# Connectors.net
KiCad netlist of a schematic drawn in Altium Designer
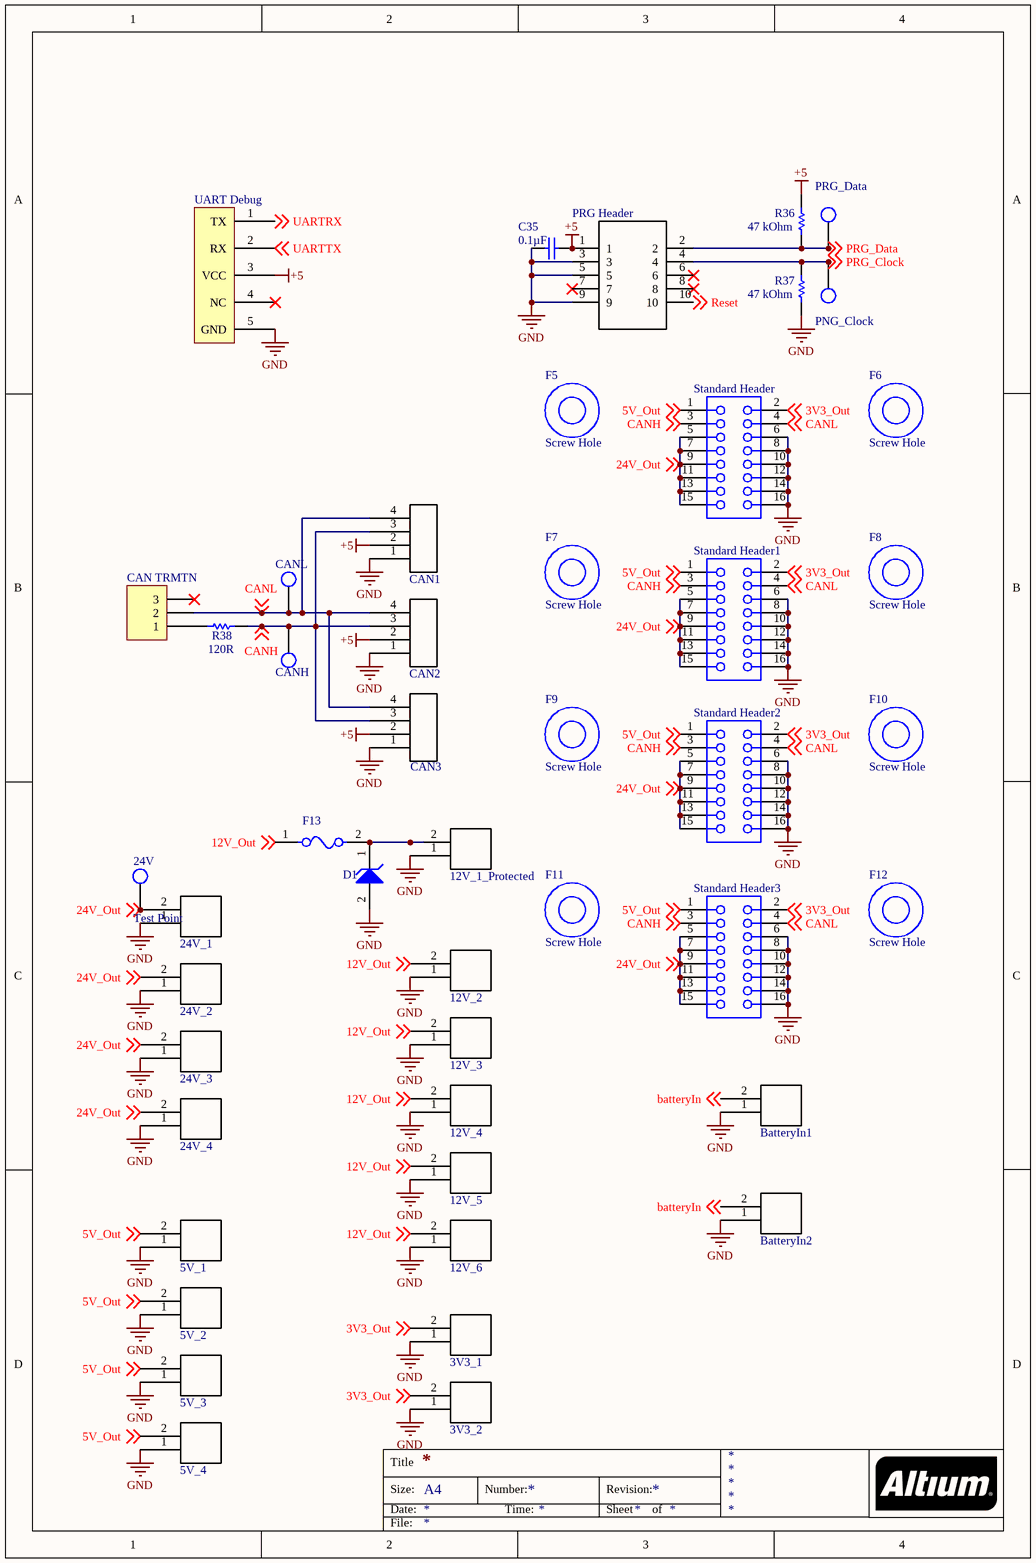
[diagram p0: Connectors.SchDoc]

(export (version "E")
  (design (tool "Eeschema 10.0.6"))
  (components
    (comp (ref "3V3_1")
      (value "Molex 6.5MM  power connector")
      (footprint "power connector")
      (libsource (lib "Husky Robotics Standard Library 2019-2020") (part "Molex 6.5MM  power connector"))
    )
    (comp (ref "3V3_2")
      (value "Molex 6.5MM  power connector")
      (footprint "power connector")
      (libsource (lib "Husky Robotics Standard Library 2019-2020") (part "Molex 6.5MM  power connector"))
    )
    (comp (ref "5V_1")
      (value "Molex 6.5MM  power connector")
      (footprint "power connector")
      (libsource (lib "Husky Robotics Standard Library 2019-2020") (part "Molex 6.5MM  power connector"))
    )
    (comp (ref "5V_2")
      (value "Molex 6.5MM  power connector")
      (footprint "power connector")
      (libsource (lib "Husky Robotics Standard Library 2019-2020") (part "Molex 6.5MM  power connector"))
    )
    (comp (ref "5V_3")
      (value "Molex 6.5MM  power connector")
      (footprint "power connector")
      (libsource (lib "Husky Robotics Standard Library 2019-2020") (part "Molex 6.5MM  power connector"))
    )
    (comp (ref "5V_4")
      (value "Molex 6.5MM  power connector")
      (footprint "power connector")
      (libsource (lib "Husky Robotics Standard Library 2019-2020") (part "Molex 6.5MM  power connector"))
    )
    (comp (ref "12V_1_Protected")
      (value "Molex 6.5MM  power connector")
      (footprint "power connector")
      (libsource (lib "Husky Robotics Standard Library 2019-2020") (part "Molex 6.5MM  power connector"))
    )
    (comp (ref "12V_2")
      (value "Molex 6.5MM  power connector")
      (footprint "power connector")
      (libsource (lib "Husky Robotics Standard Library 2019-2020") (part "Molex 6.5MM  power connector"))
    )
    (comp (ref "12V_3")
      (value "Molex 6.5MM  power connector")
      (footprint "power connector")
      (libsource (lib "Husky Robotics Standard Library 2019-2020") (part "Molex 6.5MM  power connector"))
    )
    (comp (ref "12V_4")
      (value "Molex 6.5MM  power connector")
      (footprint "power connector")
      (libsource (lib "Husky Robotics Standard Library 2019-2020") (part "Molex 6.5MM  power connector"))
    )
    (comp (ref "12V_5")
      (value "Molex 6.5MM  power connector")
      (footprint "power connector")
      (libsource (lib "Husky Robotics Standard Library 2019-2020") (part "Molex 6.5MM  power connector"))
    )
    (comp (ref "12V_6")
      (value "Molex 6.5MM  power connector")
      (footprint "power connector")
      (libsource (lib "Husky Robotics Standard Library 2019-2020") (part "Molex 6.5MM  power connector"))
    )
    (comp (ref "24V")
      (value "Test Point")
      (footprint "Test Point Through-hole")
      (libsource (lib "University of Washington - Husky Robotics Team") (part "Test Point"))
    )
    (comp (ref "24V_1")
      (value "Molex 6.5MM  power connector")
      (footprint "power connector")
      (libsource (lib "Husky Robotics Standard Library 2019-2020") (part "Molex 6.5MM  power connector"))
    )
    (comp (ref "24V_2")
      (value "Molex 6.5MM  power connector")
      (footprint "power connector")
      (libsource (lib "Husky Robotics Standard Library 2019-2020") (part "Molex 6.5MM  power connector"))
    )
    (comp (ref "24V_3")
      (value "Molex 6.5MM  power connector")
      (footprint "power connector")
      (libsource (lib "Husky Robotics Standard Library 2019-2020") (part "Molex 6.5MM  power connector"))
    )
    (comp (ref "24V_4")
      (value "Molex 6.5MM  power connector")
      (footprint "power connector")
      (libsource (lib "Husky Robotics Standard Library 2019-2020") (part "Molex 6.5MM  power connector"))
    )
    (comp (ref "BatteryIn1")
      (value "Super Saber")
      (footprint "Super Sabre")
      (libsource (lib "Husky Robotics Standard Library 2019-2020") (part "Super Saber"))
    )
    (comp (ref "BatteryIn2")
      (value "Super Saber")
      (footprint "Super Sabre")
      (libsource (lib "Husky Robotics Standard Library 2019-2020") (part "Super Saber"))
    )
    (comp (ref "C35")
      (value "Capacitor 0805")
      (footprint "Cap 0805")
      (description "Standard Capacitor")
      (fields (field (name "MANUFACTURER") "AVX") (field (name "CAPACITANCE") "0.1µF"))
      (libsource (lib "Standard Cap") (part "Capacitor 0805"))
    )
    (comp (ref "CAN TRMTN")
      (value "Header 3")
      (footprint "HDR1X3")
      (description "Header, 3-Pin")
      (fields (field (name "PUBLISHER") "Altium Limited"))
      (libsource (lib "Miscellaneous Connectors") (part "Header 3"))
    )
    (comp (ref "CAN1")
      (value "Molex Micro")
      (footprint "microfit 4 pin")
      (description "Molex micro-fit 3.0 dual row header. P/N 0430450427")
      (libsource (lib "Husky Robotics Standard Library 2019-2020") (part "Molex micro-fit 4-pin (Single row schematic)"))
    )
    (comp (ref "CAN2")
      (value "Molex Micro")
      (footprint "microfit 4 pin")
      (description "Molex micro-fit 3.0 dual row header. P/N 0430450427")
      (libsource (lib "Husky Robotics Standard Library 2019-2020") (part "Molex micro-fit 4-pin (Single row schematic)"))
    )
    (comp (ref "CAN3")
      (value "Molex Micro")
      (footprint "microfit 4 pin")
      (description "Molex micro-fit 3.0 dual row header. P/N 0430450427")
      (libsource (lib "Husky Robotics Standard Library 2019-2020") (part "Molex micro-fit 4-pin (Single row schematic)"))
    )
    (comp (ref "CANH")
      (value "Test Point")
      (footprint "Test Point Through-hole")
      (libsource (lib "Husky Robotics Standard Library 2019-2020") (part "Test Point"))
    )
    (comp (ref "CANL")
      (value "Test Point")
      (footprint "Test Point Through-hole")
      (libsource (lib "Husky Robotics Standard Library 2019-2020") (part "Test Point"))
    )
    (comp (ref "D1")
      (value "1SMB5928BT3G")
      (footprint "ONSC-SMB-2-403A-03_H_V")
      (description "3 W Zener Voltage Regulator, 2-Pin SMB, Pb-Free, Tape and Reel")
      (fields (field (name "MANUFACTURER") "On Semiconductor"))
      (libsource (lib "Altium Content Vault") (part "ONSC-K1A2-2"))
    )
    (comp (ref "F5")
      (value "Screw Hole")
      (footprint "Screw Hole")
      (description "Add 4 of these to your design for screw hole mounting")
      (libsource (lib "Husky Robotics Standard Library 2019-2020") (part "Screw Hole"))
    )
    (comp (ref "F6")
      (value "Screw Hole")
      (footprint "Screw Hole")
      (description "Add 4 of these to your design for screw hole mounting")
      (libsource (lib "Husky Robotics Standard Library 2019-2020") (part "Screw Hole"))
    )
    (comp (ref "F7")
      (value "Screw Hole")
      (footprint "Screw Hole")
      (description "Add 4 of these to your design for screw hole mounting")
      (libsource (lib "Husky Robotics Standard Library 2019-2020") (part "Screw Hole"))
    )
    (comp (ref "F8")
      (value "Screw Hole")
      (footprint "Screw Hole")
      (description "Add 4 of these to your design for screw hole mounting")
      (libsource (lib "Husky Robotics Standard Library 2019-2020") (part "Screw Hole"))
    )
    (comp (ref "F9")
      (value "Screw Hole")
      (footprint "Screw Hole")
      (description "Add 4 of these to your design for screw hole mounting")
      (libsource (lib "Husky Robotics Standard Library 2019-2020") (part "Screw Hole"))
    )
    (comp (ref "F10")
      (value "Screw Hole")
      (footprint "Screw Hole")
      (description "Add 4 of these to your design for screw hole mounting")
      (libsource (lib "Husky Robotics Standard Library 2019-2020") (part "Screw Hole"))
    )
    (comp (ref "F11")
      (value "Screw Hole")
      (footprint "Screw Hole")
      (description "Add 4 of these to your design for screw hole mounting")
      (libsource (lib "Husky Robotics Standard Library 2019-2020") (part "Screw Hole"))
    )
    (comp (ref "F12")
      (value "Screw Hole")
      (footprint "Screw Hole")
      (description "Add 4 of these to your design for screw hole mounting")
      (libsource (lib "Husky Robotics Standard Library 2019-2020") (part "Screw Hole"))
    )
    (comp (ref "F13")
      (value "015402.5DRT")
      (footprint "FP-0154-MFG")
      (description "FUSE BRD MNT 2.5A 125VAC/VDC SMD")
      (fields
        (field (name "OCTOPART") "https://octopart.com/015402.5drt-littelfuse-565920")
        (field (name "MANUFACTURER") "Littelfuse")
      )
      (libsource (lib "Altium Content Vault") (part "5bcf9b9f640e542cf0359d10258e979"))
    )
    (comp (ref "PNG_Clock")
      (value "Test Point")
      (footprint "Test Point Through-hole")
      (libsource (lib "Husky Robotics Standard Library 2019-2020") (part "Test Point"))
    )
    (comp (ref "PRG Header")
      (value "Programming Header")
      (footprint "programming3D")
      (libsource (lib "Husky Robotics Standard Library 2019-2020") (part "Programming Header"))
    )
    (comp (ref "PRG_Data")
      (value "Test Point")
      (footprint "Test Point Through-hole")
      (libsource (lib "Husky Robotics Standard Library 2019-2020") (part "Test Point"))
    )
    (comp (ref "R36")
      (value "47 kOhm")
      (footprint "RESC0805(2012)_N")
      (description "Generic 0805 Resistor")
      (fields (field (name "TOLERANCE") "5 %") (field (name "POWER") "0.125 W"))
      (libsource (lib "Husky Robotics Standard Library 2019-2020") (part "Resistor 0805"))
    )
    (comp (ref "R37")
      (value "47 kOhm")
      (footprint "RESC0805(2012)_N")
      (description "Generic 0805 Resistor")
      (fields
        (field (name "TOLERANCE") "5 %")
        (field (name "POWER") "0.125 W")
        (field (name "SOURCE") "CAN Termination Resistor 0805.SchLib")
      )
      (libsource (lib "University of Washington - Husky Robotics Team") (part "Resistor 0805"))
    )
    (comp (ref "R38")
      (value "120R")
      (footprint "RESC0805(2012)_N")
      (description "Generic 0805 Resistor")
      (fields (field (name "TOLERANCE") "5 %") (field (name "POWER") "0.125 W"))
      (libsource (lib "Husky Robotics Standard Library 2019-2020") (part "Resistor 0805"))
    )
    (comp (ref "Standard Header")
      (value "Stacking Header")
      (footprint "SMTC-SSQ-108-02-X-D")
      (description "SQ Post Socket, Through-hole, Vertical, -55 to 125 degC, 2.54 mm Pitch, 16-Pin, Female, RoHS")
      (fields (field (name "MANUFACTURER") "Samtec") (field (name "PARTNUMBER") "SSQ-108-02-G-D"))
      (libsource (lib "Husky Robotics Standard Library 2019-2020") (part "Stacking Header"))
    )
    (comp (ref "Standard Header1")
      (value "Stacking Header")
      (footprint "SMTC-SSQ-108-02-X-D")
      (description "SQ Post Socket, Through-hole, Vertical, -55 to 125 degC, 2.54 mm Pitch, 16-Pin, Female, RoHS")
      (fields (field (name "MANUFACTURER") "Samtec") (field (name "PARTNUMBER") "SSQ-108-02-G-D"))
      (libsource (lib "Husky Robotics Standard Library 2019-2020") (part "Stacking Header"))
    )
    (comp (ref "Standard Header2")
      (value "Stacking Header")
      (footprint "SMTC-SSQ-108-02-X-D")
      (description "SQ Post Socket, Through-hole, Vertical, -55 to 125 degC, 2.54 mm Pitch, 16-Pin, Female, RoHS")
      (fields (field (name "MANUFACTURER") "Samtec") (field (name "PARTNUMBER") "SSQ-108-02-G-D"))
      (libsource (lib "Husky Robotics Standard Library 2019-2020") (part "Stacking Header"))
    )
    (comp (ref "Standard Header3")
      (value "Stacking Header")
      (footprint "SMTC-SSQ-108-02-X-D")
      (description "SQ Post Socket, Through-hole, Vertical, -55 to 125 degC, 2.54 mm Pitch, 16-Pin, Female, RoHS")
      (fields (field (name "MANUFACTURER") "Samtec") (field (name "PARTNUMBER") "SSQ-108-02-G-D"))
      (libsource (lib "Husky Robotics Standard Library 2019-2020") (part "Stacking Header"))
    )
    (comp (ref "UART Debug")
      (value "UART Debuging Header")
      (footprint "UART Debugging Header")
      (libsource (lib "Husky Robotics Standard Library 2019-2020") (part "UART Debuging Header"))
    )
  )
  (nets
    (net (code "1") (name "+5") (class "Default")
      (node (ref "C35") (pin "2") (pinfunction "2_2") (pintype "passive"))
      (node (ref "CAN1") (pin "2") (pintype "passive"))
      (node (ref "CAN2") (pin "2") (pintype "passive"))
      (node (ref "CAN3") (pin "2") (pintype "passive"))
      (node (ref "PRG Header") (pin "1") (pinfunction "1_1") (pintype "passive"))
      (node (ref "R36") (pin "2") (pinfunction "2_2") (pintype "passive"))
      (node (ref "UART Debug") (pin "3") (pinfunction "VCC_3") (pintype "passive"))
    )
    (net (code "2") (name "3V3_Out") (class "Default")
      (node (ref "3V3_1") (pin "2") (pintype "passive"))
      (node (ref "3V3_2") (pin "2") (pintype "passive"))
      (node (ref "Standard Header") (pin "2") (pinfunction "2_2") (pintype "passive"))
      (node (ref "Standard Header1") (pin "2") (pinfunction "2_2") (pintype "passive"))
      (node (ref "Standard Header2") (pin "2") (pinfunction "2_2") (pintype "passive"))
      (node (ref "Standard Header3") (pin "2") (pinfunction "2_2") (pintype "passive"))
    )
    (net (code "3") (name "5V_Out") (class "Default")
      (node (ref "5V_1") (pin "2") (pintype "passive"))
      (node (ref "5V_2") (pin "2") (pintype "passive"))
      (node (ref "5V_3") (pin "2") (pintype "passive"))
      (node (ref "5V_4") (pin "2") (pintype "passive"))
      (node (ref "Standard Header") (pin "1") (pinfunction "1_1") (pintype "passive"))
      (node (ref "Standard Header1") (pin "1") (pinfunction "1_1") (pintype "passive"))
      (node (ref "Standard Header2") (pin "1") (pinfunction "1_1") (pintype "passive"))
      (node (ref "Standard Header3") (pin "1") (pinfunction "1_1") (pintype "passive"))
    )
    (net (code "4") (name "12V_Out") (class "Default")
      (node (ref "12V_2") (pin "2") (pintype "passive"))
      (node (ref "12V_3") (pin "2") (pintype "passive"))
      (node (ref "12V_4") (pin "2") (pintype "passive"))
      (node (ref "12V_5") (pin "2") (pintype "passive"))
      (node (ref "12V_6") (pin "2") (pintype "passive"))
      (node (ref "F13") (pin "1") (pinfunction "1_1") (pintype "passive"))
    )
    (net (code "5") (name "24V_Out") (class "Default")
      (node (ref "24V") (pin "1") (pinfunction "1_1") (pintype "passive"))
      (node (ref "24V_1") (pin "2") (pintype "passive"))
      (node (ref "24V_2") (pin "2") (pintype "passive"))
      (node (ref "24V_3") (pin "2") (pintype "passive"))
      (node (ref "24V_4") (pin "2") (pintype "passive"))
      (node (ref "Standard Header") (pin "11") (pinfunction "11_11") (pintype "passive"))
      (node (ref "Standard Header") (pin "13") (pinfunction "13_13") (pintype "passive"))
      (node (ref "Standard Header") (pin "15") (pinfunction "15_15") (pintype "passive"))
      (node (ref "Standard Header") (pin "5") (pinfunction "5_5") (pintype "passive"))
      (node (ref "Standard Header") (pin "7") (pinfunction "7_7") (pintype "passive"))
      (node (ref "Standard Header") (pin "9") (pinfunction "9_9") (pintype "passive"))
      (node (ref "Standard Header1") (pin "11") (pinfunction "11_11") (pintype "passive"))
      (node (ref "Standard Header1") (pin "13") (pinfunction "13_13") (pintype "passive"))
      (node (ref "Standard Header1") (pin "15") (pinfunction "15_15") (pintype "passive"))
      (node (ref "Standard Header1") (pin "5") (pinfunction "5_5") (pintype "passive"))
      (node (ref "Standard Header1") (pin "7") (pinfunction "7_7") (pintype "passive"))
      (node (ref "Standard Header1") (pin "9") (pinfunction "9_9") (pintype "passive"))
      (node (ref "Standard Header2") (pin "11") (pinfunction "11_11") (pintype "passive"))
      (node (ref "Standard Header2") (pin "13") (pinfunction "13_13") (pintype "passive"))
      (node (ref "Standard Header2") (pin "15") (pinfunction "15_15") (pintype "passive"))
      (node (ref "Standard Header2") (pin "5") (pinfunction "5_5") (pintype "passive"))
      (node (ref "Standard Header2") (pin "7") (pinfunction "7_7") (pintype "passive"))
      (node (ref "Standard Header2") (pin "9") (pinfunction "9_9") (pintype "passive"))
      (node (ref "Standard Header3") (pin "11") (pinfunction "11_11") (pintype "passive"))
      (node (ref "Standard Header3") (pin "13") (pinfunction "13_13") (pintype "passive"))
      (node (ref "Standard Header3") (pin "15") (pinfunction "15_15") (pintype "passive"))
      (node (ref "Standard Header3") (pin "5") (pinfunction "5_5") (pintype "passive"))
      (node (ref "Standard Header3") (pin "7") (pinfunction "7_7") (pintype "passive"))
      (node (ref "Standard Header3") (pin "9") (pinfunction "9_9") (pintype "passive"))
    )
    (net (code "6") (name "CANH") (class "Default")
      (node (ref "CAN1") (pin "3") (pintype "passive"))
      (node (ref "CAN2") (pin "3") (pintype "passive"))
      (node (ref "CAN3") (pin "3") (pintype "passive"))
      (node (ref "CANH") (pin "1") (pinfunction "1_1") (pintype "passive"))
      (node (ref "R38") (pin "2") (pinfunction "2_2") (pintype "passive"))
      (node (ref "Standard Header") (pin "3") (pinfunction "3_3") (pintype "passive"))
      (node (ref "Standard Header1") (pin "3") (pinfunction "3_3") (pintype "passive"))
      (node (ref "Standard Header2") (pin "3") (pinfunction "3_3") (pintype "passive"))
      (node (ref "Standard Header3") (pin "3") (pinfunction "3_3") (pintype "passive"))
    )
    (net (code "7") (name "CANL") (class "Default")
      (node (ref "CAN TRMTN") (pin "2") (pinfunction "2_2") (pintype "passive"))
      (node (ref "CAN1") (pin "4") (pintype "passive"))
      (node (ref "CAN2") (pin "4") (pintype "passive"))
      (node (ref "CAN3") (pin "4") (pintype "passive"))
      (node (ref "CANL") (pin "1") (pinfunction "1_1") (pintype "passive"))
      (node (ref "Standard Header") (pin "4") (pinfunction "4_4") (pintype "passive"))
      (node (ref "Standard Header1") (pin "4") (pinfunction "4_4") (pintype "passive"))
      (node (ref "Standard Header2") (pin "4") (pinfunction "4_4") (pintype "passive"))
      (node (ref "Standard Header3") (pin "4") (pinfunction "4_4") (pintype "passive"))
    )
    (net (code "8") (name "GND") (class "Default")
      (node (ref "12V_1_Protected") (pin "1") (pintype "passive"))
      (node (ref "12V_2") (pin "1") (pintype "passive"))
      (node (ref "12V_3") (pin "1") (pintype "passive"))
      (node (ref "12V_4") (pin "1") (pintype "passive"))
      (node (ref "12V_5") (pin "1") (pintype "passive"))
      (node (ref "12V_6") (pin "1") (pintype "passive"))
      (node (ref "24V_1") (pin "1") (pintype "passive"))
      (node (ref "24V_2") (pin "1") (pintype "passive"))
      (node (ref "24V_3") (pin "1") (pintype "passive"))
      (node (ref "24V_4") (pin "1") (pintype "passive"))
      (node (ref "3V3_1") (pin "1") (pintype "passive"))
      (node (ref "3V3_2") (pin "1") (pintype "passive"))
      (node (ref "5V_1") (pin "1") (pintype "passive"))
      (node (ref "5V_2") (pin "1") (pintype "passive"))
      (node (ref "5V_3") (pin "1") (pintype "passive"))
      (node (ref "5V_4") (pin "1") (pintype "passive"))
      (node (ref "BatteryIn1") (pin "1") (pintype "passive"))
      (node (ref "BatteryIn2") (pin "1") (pintype "passive"))
      (node (ref "C35") (pin "1") (pinfunction "1_1") (pintype "passive"))
      (node (ref "CAN1") (pin "1") (pintype "passive"))
      (node (ref "CAN2") (pin "1") (pintype "passive"))
      (node (ref "CAN3") (pin "1") (pintype "passive"))
      (node (ref "D1") (pin "2") (pinfunction "A_2") (pintype "passive"))
      (node (ref "PRG Header") (pin "3") (pinfunction "3_3") (pintype "passive"))
      (node (ref "PRG Header") (pin "5") (pinfunction "5_5") (pintype "passive"))
      (node (ref "PRG Header") (pin "9") (pinfunction "9_9") (pintype "passive"))
      (node (ref "R37") (pin "1") (pinfunction "1_1") (pintype "passive"))
      (node (ref "Standard Header") (pin "10") (pinfunction "10_10") (pintype "passive"))
      (node (ref "Standard Header") (pin "12") (pinfunction "12_12") (pintype "passive"))
      (node (ref "Standard Header") (pin "14") (pinfunction "14_14") (pintype "passive"))
      (node (ref "Standard Header") (pin "16") (pinfunction "16_16") (pintype "passive"))
      (node (ref "Standard Header") (pin "6") (pinfunction "6_6") (pintype "passive"))
      (node (ref "Standard Header") (pin "8") (pinfunction "8_8") (pintype "passive"))
      (node (ref "Standard Header1") (pin "10") (pinfunction "10_10") (pintype "passive"))
      (node (ref "Standard Header1") (pin "12") (pinfunction "12_12") (pintype "passive"))
      (node (ref "Standard Header1") (pin "14") (pinfunction "14_14") (pintype "passive"))
      (node (ref "Standard Header1") (pin "16") (pinfunction "16_16") (pintype "passive"))
      (node (ref "Standard Header1") (pin "6") (pinfunction "6_6") (pintype "passive"))
      (node (ref "Standard Header1") (pin "8") (pinfunction "8_8") (pintype "passive"))
      (node (ref "Standard Header2") (pin "10") (pinfunction "10_10") (pintype "passive"))
      (node (ref "Standard Header2") (pin "12") (pinfunction "12_12") (pintype "passive"))
      (node (ref "Standard Header2") (pin "14") (pinfunction "14_14") (pintype "passive"))
      (node (ref "Standard Header2") (pin "16") (pinfunction "16_16") (pintype "passive"))
      (node (ref "Standard Header2") (pin "6") (pinfunction "6_6") (pintype "passive"))
      (node (ref "Standard Header2") (pin "8") (pinfunction "8_8") (pintype "passive"))
      (node (ref "Standard Header3") (pin "10") (pinfunction "10_10") (pintype "passive"))
      (node (ref "Standard Header3") (pin "12") (pinfunction "12_12") (pintype "passive"))
      (node (ref "Standard Header3") (pin "14") (pinfunction "14_14") (pintype "passive"))
      (node (ref "Standard Header3") (pin "16") (pinfunction "16_16") (pintype "passive"))
      (node (ref "Standard Header3") (pin "6") (pinfunction "6_6") (pintype "passive"))
      (node (ref "Standard Header3") (pin "8") (pinfunction "8_8") (pintype "passive"))
      (node (ref "UART Debug") (pin "5") (pinfunction "GND_5") (pintype "passive"))
    )
    (net (code "9") (name "Net-(CAN TRMTN-Pad1)") (class "Default")
      (node (ref "CAN TRMTN") (pin "1") (pinfunction "1_1") (pintype "passive"))
      (node (ref "R38") (pin "1") (pinfunction "1_1") (pintype "passive"))
    )
    (net (code "10") (name "Net-(D1-K)") (class "Default")
      (node (ref "12V_1_Protected") (pin "2") (pintype "passive"))
      (node (ref "D1") (pin "1") (pinfunction "K_1") (pintype "passive"))
      (node (ref "F13") (pin "2") (pinfunction "2_2") (pintype "passive"))
    )
    (net (code "11") (name "PRG_Clock") (class "Default")
      (node (ref "PNG_Clock") (pin "1") (pinfunction "1_1") (pintype "passive"))
      (node (ref "PRG Header") (pin "4") (pinfunction "4_4") (pintype "passive"))
      (node (ref "R37") (pin "2") (pinfunction "2_2") (pintype "passive"))
    )
    (net (code "12") (name "PRG_Data") (class "Default")
      (node (ref "PRG Header") (pin "2") (pinfunction "2_2") (pintype "passive"))
      (node (ref "PRG_Data") (pin "1") (pinfunction "1_1") (pintype "passive"))
      (node (ref "R36") (pin "1") (pinfunction "1_1") (pintype "passive"))
    )
    (net (code "13") (name "Reset") (class "Default")
      (node (ref "PRG Header") (pin "10") (pinfunction "10_10") (pintype "passive"))
    )
    (net (code "14") (name "UARTRX") (class "Default")
      (node (ref "UART Debug") (pin "1") (pinfunction "TX_1") (pintype "passive"))
    )
    (net (code "15") (name "UARTTX") (class "Default")
      (node (ref "UART Debug") (pin "2") (pinfunction "RX_2") (pintype "passive"))
    )
    (net (code "16") (name "batteryIn") (class "Default")
      (node (ref "BatteryIn1") (pin "2") (pintype "passive"))
      (node (ref "BatteryIn2") (pin "2") (pintype "passive"))
    )
    (net (code "17") (name "unconnected-(CAN TRMTN-Pad3)") (class "Default")
      (node (ref "CAN TRMTN") (pin "3") (pinfunction "3_3") (pintype "passive+no_connect"))
    )
    (net (code "18") (name "unconnected-(PRG Header-Pad6)") (class "Default")
      (node (ref "PRG Header") (pin "6") (pinfunction "6_6") (pintype "passive+no_connect"))
    )
    (net (code "19") (name "unconnected-(PRG Header-Pad7)") (class "Default")
      (node (ref "PRG Header") (pin "7") (pinfunction "7_7") (pintype "passive+no_connect"))
    )
    (net (code "20") (name "unconnected-(PRG Header-Pad8)") (class "Default")
      (node (ref "PRG Header") (pin "8") (pinfunction "8_8") (pintype "passive+no_connect"))
    )
    (net (code "21") (name "unconnected-(UART Debug-NC-Pad4)") (class "Default")
      (node (ref "UART Debug") (pin "4") (pinfunction "NC_4") (pintype "passive+no_connect"))
    )
  )
)
